# EIT_Teensy_PSU.net
KiCad netlist of a schematic drawn in Altium Designer
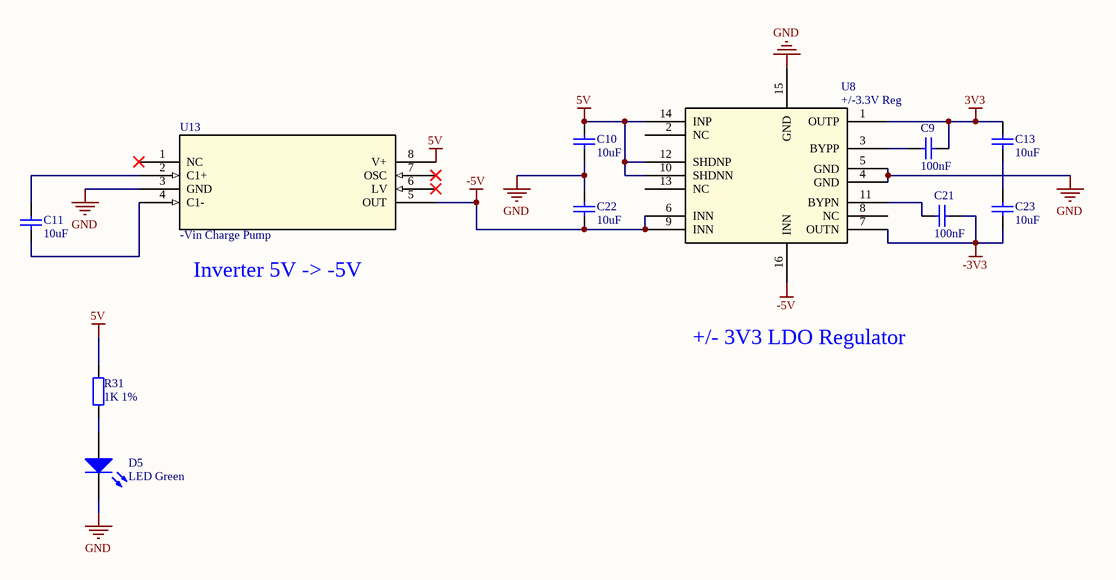
[diagram p0: EIT_Teensy_PSU.SchDoc]

(export (version "E")
  (design (tool "Eeschema 10.0.6"))
  (components
    (comp (ref "C9")
      (value "100nF")
      (footprint "0603 CAP")
      (description "Multi Layer Ceramic Capacitor (MLCC) / Cap Ceramic 0.1uF 50V X7R 10% Pad SMD 0603 125°C T/R")
      (fields
        (field (name "MANUFACTURER") "Samsung")
        (field (name "MANUFACTURER PART NUMBER") "CL10B104KB8NNNC")
      )
      (libsource (lib "EitLib") (part "Cap 0603 100nF 10% 50V"))
    )
    (comp (ref "C10")
      (value "10uF")
      (footprint "0603 CAP")
      (description "0603 10 uF 25 V ±20 % Tolerance X5R Surface Mount Multilayer Ceramic Capacitor")
      (fields
        (field (name "MANUFACTURER") "Murata")
        (field (name "MANUFACTURER PART NUMBER") "GRT188R61E106ME13D")
      )
      (libsource (lib "EitLib") (part "Cap 0603 10uF 10% 25V"))
    )
    (comp (ref "C11")
      (value "10uF")
      (footprint "0603 CAP")
      (description "0603 10 uF 25 V ±20 % Tolerance X5R Surface Mount Multilayer Ceramic Capacitor")
      (fields
        (field (name "MANUFACTURER") "Murata")
        (field (name "MANUFACTURER PART NUMBER") "GRT188R61E106ME13D")
      )
      (libsource (lib "EitLib") (part "Cap 0603 10uF 10% 25V"))
    )
    (comp (ref "C13")
      (value "10uF")
      (footprint "0603 CAP")
      (description "0603 10 uF 25 V ±20 % Tolerance X5R Surface Mount Multilayer Ceramic Capacitor")
      (fields
        (field (name "MANUFACTURER") "Murata")
        (field (name "MANUFACTURER PART NUMBER") "GRT188R61E106ME13D")
      )
      (libsource (lib "EitLib") (part "Cap 0603 10uF 10% 25V"))
    )
    (comp (ref "C21")
      (value "100nF")
      (footprint "0603 CAP")
      (description "Multi Layer Ceramic Capacitor (MLCC) / Cap Ceramic 0.1uF 50V X7R 10% Pad SMD 0603 125°C T/R")
      (fields
        (field (name "MANUFACTURER") "Samsung")
        (field (name "MANUFACTURER PART NUMBER") "CL10B104KB8NNNC")
      )
      (libsource (lib "EitLib") (part "Cap 0603 100nF 10% 50V"))
    )
    (comp (ref "C22")
      (value "10uF")
      (footprint "0603 CAP")
      (description "0603 10 uF 25 V ±20 % Tolerance X5R Surface Mount Multilayer Ceramic Capacitor")
      (fields
        (field (name "MANUFACTURER") "Murata")
        (field (name "MANUFACTURER PART NUMBER") "GRT188R61E106ME13D")
      )
      (libsource (lib "EitLib") (part "Cap 0603 10uF 10% 25V"))
    )
    (comp (ref "C23")
      (value "10uF")
      (footprint "0603 CAP")
      (description "0603 10 uF 25 V ±20 % Tolerance X5R Surface Mount Multilayer Ceramic Capacitor")
      (fields
        (field (name "MANUFACTURER") "Murata")
        (field (name "MANUFACTURER PART NUMBER") "GRT188R61E106ME13D")
      )
      (libsource (lib "EitLib") (part "Cap 0603 10uF 10% 25V"))
    )
    (comp (ref "D5")
      (value "LED Green")
      (footprint "0603 LED")
      (description "LED GREEN DIFFUSED 0603 SMD")
      (fields
        (field (name "MANUFACTURER") "Osram Opto")
        (field (name "MANUFACTURER PART NUMBER") "LG Q396-PS-35")
      )
      (libsource (lib "EitLib") (part "LED Green 0603 2V"))
    )
    (comp (ref "R31")
      (value "1K 1%")
      (footprint "0603 RES")
      (description "RES SMD 1K OHM 1% 1/10W 0603")
      (fields
        (field (name "MANUFACTURER") "Yageo")
        (field (name "MANUFACTURER PART NUMBER") "RC0603FR-071KL")
      )
      (libsource (lib "EitLib") (part "Res 0603 1K 1%"))
    )
    (comp (ref "U8")
      (value "+/-3.3V Reg")
      (footprint "14-DFN")
      (description "IC REG LINEAR +-3.3V 14DFN")
      (fields
        (field (name "MANUFACTURER") "Analog Devices / Linear Technology")
        (field (name "MANUFACTURER PART NUMBER") "LT3032EDE-3.3#PBF")
      )
      (libsource (lib "EitLib") (part "IC Reg LDO +/-3.3V 150mA"))
    )
    (comp (ref "U13")
      (value "-Vin Charge Pump")
      (footprint "8-SOIC")
      (description "Charge Pump -Vin -10V 8-Pin SOIC T/R")
      (fields
        (field (name "MANUFACTURER") "TI National Semiconductor")
        (field (name "MANUFACTURER PART NUMBER") "LMC7660IMX/NOPB")
      )
      (libsource (lib "EitLib") (part "LMC7660IMX/NOPB"))
    )
  )
  (nets
    (net (code "1") (name "-3V3") (class "Default")
      (node (ref "C21") (pin "2") (pinfunction "2_2") (pintype "passive"))
      (node (ref "C23") (pin "1") (pinfunction "1_1") (pintype "passive"))
      (node (ref "U8") (pin "7") (pinfunction "OUTN_7") (pintype "power_in"))
    )
    (net (code "2") (name "-5V") (class "Default")
      (node (ref "C22") (pin "1") (pinfunction "1_1") (pintype "passive"))
      (node (ref "U13") (pin "5") (pinfunction "OUT_5") (pintype "power_in"))
      (node (ref "U8") (pin "16") (pinfunction "INN_16") (pintype "power_in"))
      (node (ref "U8") (pin "6") (pinfunction "INN_6") (pintype "power_in"))
      (node (ref "U8") (pin "9") (pinfunction "INN_9") (pintype "power_in"))
    )
    (net (code "3") (name "3V3") (class "Default")
      (node (ref "C13") (pin "2") (pinfunction "2_2") (pintype "passive"))
      (node (ref "C9") (pin "2") (pinfunction "2_2") (pintype "passive"))
      (node (ref "U8") (pin "1") (pinfunction "OUTP_1") (pintype "power_in"))
    )
    (net (code "4") (name "5V") (class "Default")
      (node (ref "C10") (pin "2") (pinfunction "2_2") (pintype "passive"))
      (node (ref "R31") (pin "1") (pinfunction "1_1") (pintype "passive"))
      (node (ref "U13") (pin "8") (pinfunction "V+_8") (pintype "power_in"))
      (node (ref "U8") (pin "10") (pinfunction "SHDNN_10") (pintype "passive"))
      (node (ref "U8") (pin "12") (pinfunction "SHDNP_12") (pintype "passive"))
      (node (ref "U8") (pin "14") (pinfunction "INP_14") (pintype "power_in"))
    )
    (net (code "5") (name "GND") (class "Default")
      (node (ref "C10") (pin "1") (pinfunction "1_1") (pintype "passive"))
      (node (ref "C22") (pin "2") (pinfunction "2_2") (pintype "passive"))
      (node (ref "D5") (pin "2") (pinfunction "K_2") (pintype "passive"))
      (node (ref "U13") (pin "3") (pinfunction "GND_3") (pintype "power_in"))
      (node (ref "U8") (pin "15") (pinfunction "GND_15") (pintype "power_in"))
      (node (ref "U8") (pin "4") (pinfunction "GND_4") (pintype "power_in"))
      (node (ref "U8") (pin "5") (pinfunction "GND_5") (pintype "power_in"))
    )
    (net (code "6") (name "Net-(C13-Pad1)") (class "Default")
      (node (ref "C13") (pin "1") (pinfunction "1_1") (pintype "passive"))
      (node (ref "C23") (pin "2") (pinfunction "2_2") (pintype "passive"))
    )
    (net (code "7") (name "Net-(D5-A)") (class "Default")
      (node (ref "D5") (pin "1") (pinfunction "A_1") (pintype "passive"))
      (node (ref "R31") (pin "2") (pinfunction "2_2") (pintype "passive"))
    )
    (net (code "8") (name "Net-(U8-BYPN)") (class "Default")
      (node (ref "C21") (pin "1") (pinfunction "1_1") (pintype "passive"))
      (node (ref "U8") (pin "11") (pinfunction "BYPN_11") (pintype "passive"))
    )
    (net (code "9") (name "Net-(U8-BYPP)") (class "Default")
      (node (ref "C9") (pin "1") (pinfunction "1_1") (pintype "passive"))
      (node (ref "U8") (pin "3") (pinfunction "BYPP_3") (pintype "passive"))
    )
    (net (code "10") (name "Net-(U13-C1+)") (class "Default")
      (node (ref "C11") (pin "2") (pinfunction "2_2") (pintype "passive"))
      (node (ref "U13") (pin "2") (pinfunction "C1+_2") (pintype "input"))
    )
    (net (code "11") (name "Net-(U13-C1-)") (class "Default")
      (node (ref "C11") (pin "1") (pinfunction "1_1") (pintype "passive"))
      (node (ref "U13") (pin "4") (pinfunction "C1-_4") (pintype "input"))
    )
    (net (code "12") (name "unconnected-(U8-NC-Pad2)") (class "Default")
      (node (ref "U8") (pin "2") (pinfunction "NC_2") (pintype "passive"))
    )
    (net (code "13") (name "unconnected-(U8-NC-Pad8)") (class "Default")
      (node (ref "U8") (pin "8") (pinfunction "NC_8") (pintype "passive"))
    )
    (net (code "14") (name "unconnected-(U8-NC-Pad13)") (class "Default")
      (node (ref "U8") (pin "13") (pinfunction "NC_13") (pintype "passive"))
    )
    (net (code "15") (name "unconnected-(U13-LV-Pad6)") (class "Default")
      (node (ref "U13") (pin "6") (pinfunction "LV_6") (pintype "input+no_connect"))
    )
    (net (code "16") (name "unconnected-(U13-NC-Pad1)") (class "Default")
      (node (ref "U13") (pin "1") (pinfunction "NC_1") (pintype "passive+no_connect"))
    )
    (net (code "17") (name "unconnected-(U13-OSC-Pad7)") (class "Default")
      (node (ref "U13") (pin "7") (pinfunction "OSC_7") (pintype "input+no_connect"))
    )
  )
)
